# Domino_JTAG_No_Teardrop.net
KiCad netlist of a schematic drawn in EAGLE
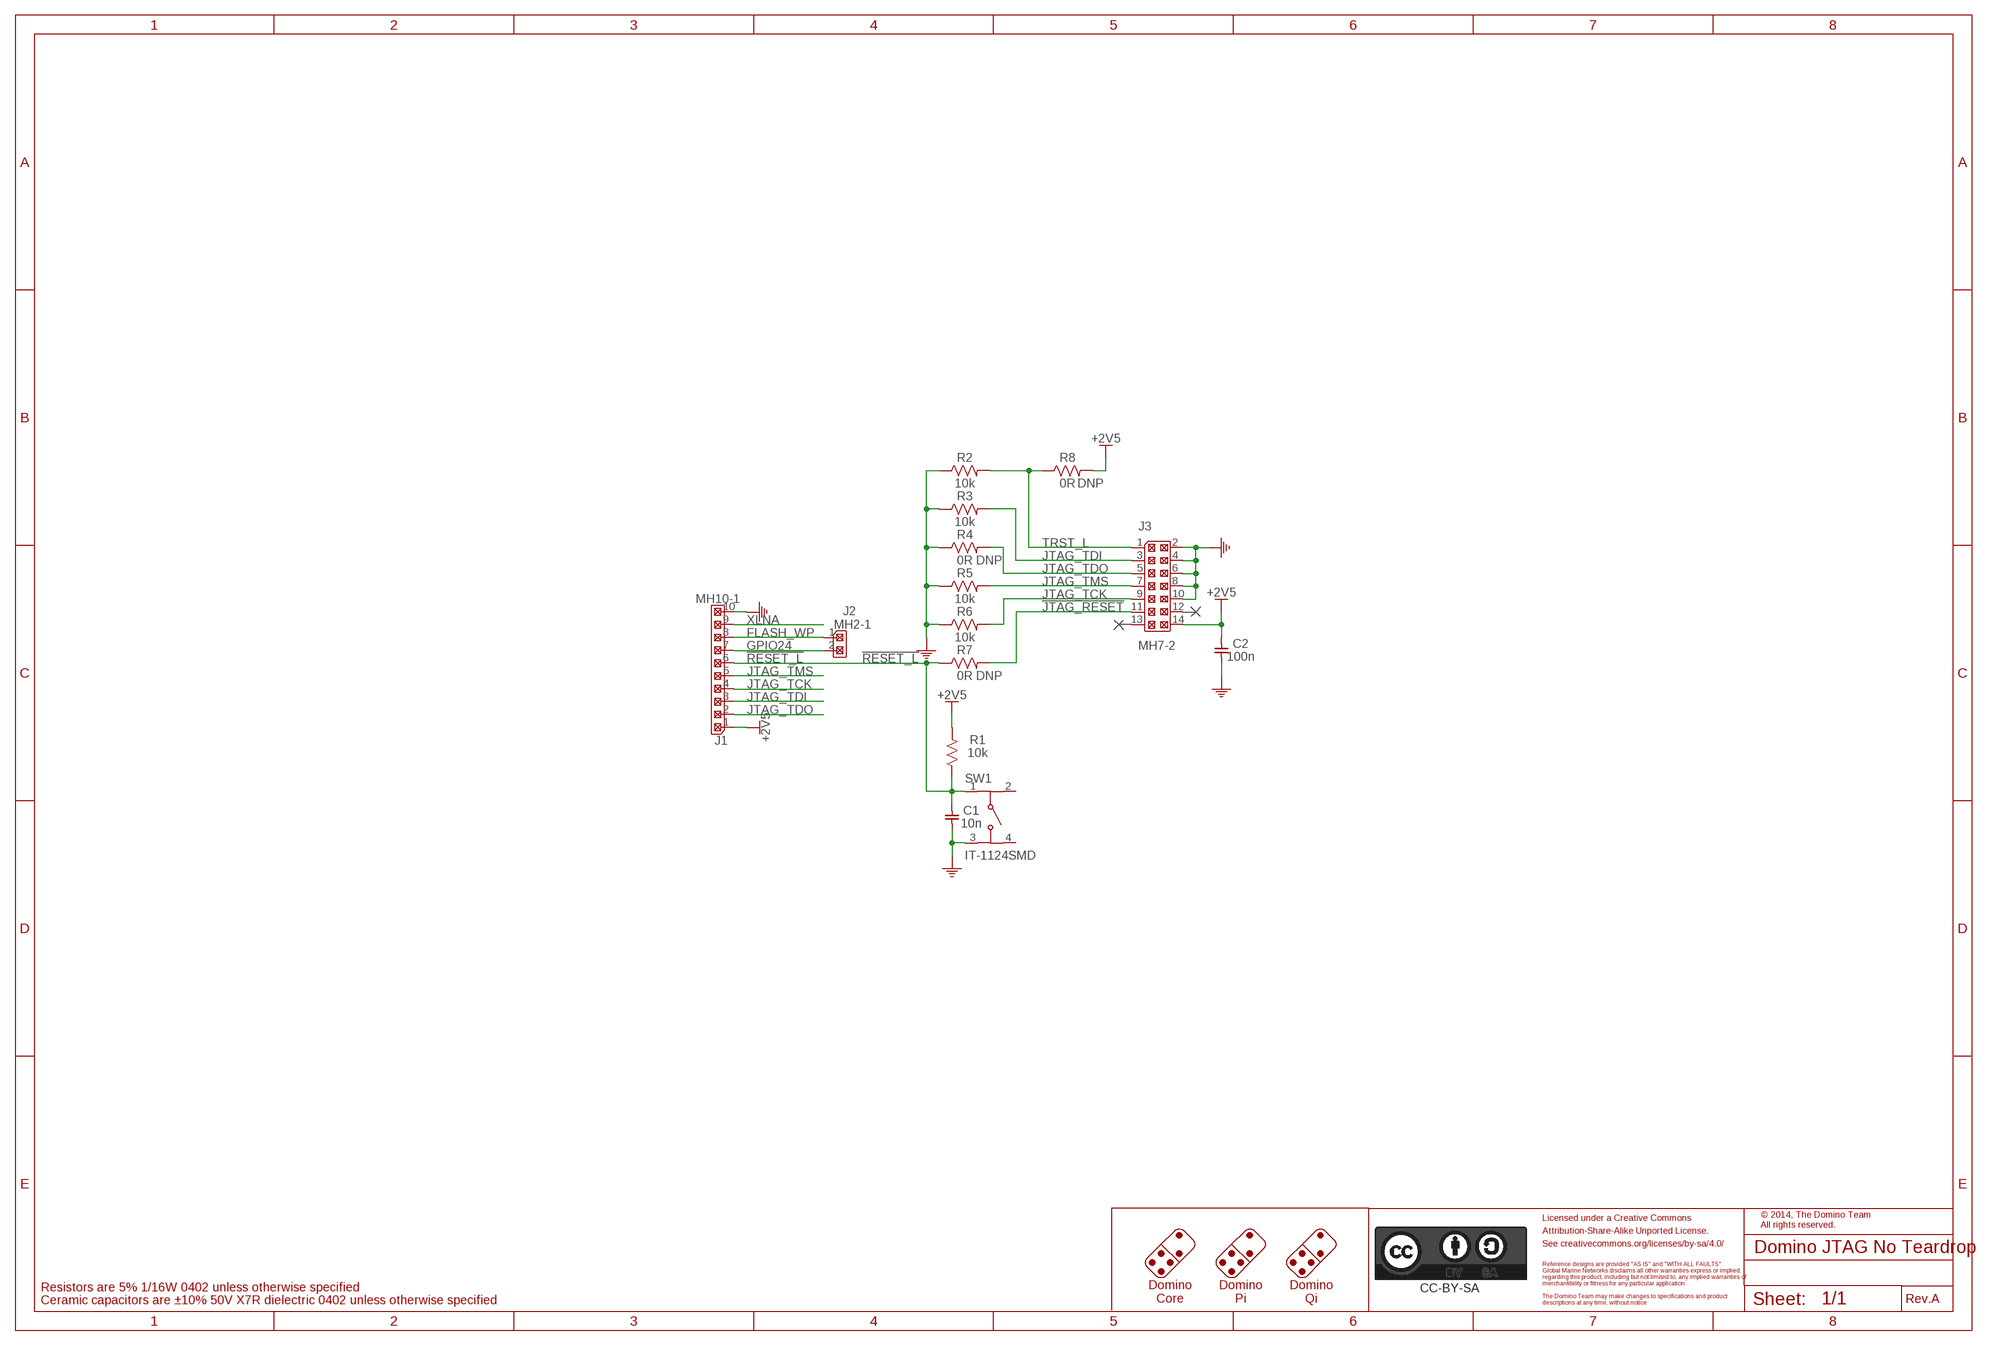
[diagram p0: schematic, sheet 1]

(export (version "E")
  (design (tool "Eeschema 10.0.6"))
  (components
    (comp (ref "C1")
      (value "10n")
      (footprint "eagle-import:C0402")
      (fields (field (name "PARTNO") "C0402_10n_X7R_10%_CER_50V"))
      (libsource (lib "eagle-import") (part "CAP_0402"))
    )
    (comp (ref "C2")
      (value "100n")
      (footprint "eagle-import:C0402")
      (fields (field (name "PARTNO") "C0402_100n_X7R_10%_CER_50V"))
      (libsource (lib "eagle-import") (part "CAP_0402"))
    )
    (comp (ref "CC-BY-SA1")
      (value "CC-BY-SA_LOGO")
      (footprint "eagle-import:CC-BY-SA_LOGO")
      (libsource (lib "eagle-import") (part "CC-BY-SA_LOGO"))
    )
    (comp (ref "J1")
      (value "MH10-1")
      (footprint "eagle-import:MH10-1-0.1")
      (fields (field (name "PARTNO") "MH10-1-0.1"))
      (libsource (lib "eagle-import") (part "MH10-1"))
    )
    (comp (ref "J2")
      (value "MH2-1")
      (footprint "eagle-import:MH2-1-0.1")
      (fields (field (name "PARTNO") "MH2-1-0.1"))
      (libsource (lib "eagle-import") (part "MH2-1"))
    )
    (comp (ref "J3")
      (value "MH7-2")
      (footprint "eagle-import:MH7-2-0.1")
      (fields (field (name "PARTNO") "MH7-2-0.1"))
      (libsource (lib "eagle-import") (part "MH7-2"))
    )
    (comp (ref "R1")
      (value "10k")
      (footprint "eagle-import:R0402")
      (fields (field (name "PARTNO") "R0402_10k_5%_62.5mW"))
      (libsource (lib "eagle-import") (part "RES_0402"))
    )
    (comp (ref "R2")
      (value "10k")
      (footprint "eagle-import:R0402")
      (fields (field (name "PARTNO") "R0402_10k_5%_62.5mW"))
      (libsource (lib "eagle-import") (part "RES_0402"))
    )
    (comp (ref "R3")
      (value "10k")
      (footprint "eagle-import:R0402")
      (fields (field (name "PARTNO") "R0402_10k_5%_62.5mW"))
      (libsource (lib "eagle-import") (part "RES_0402"))
    )
    (comp (ref "R4")
      (value "0R")
      (footprint "eagle-import:R0603")
      (fields (field (name "PARTNO") "R0603_0R_5%_125mW"))
      (libsource (lib "eagle-import") (part "RES_0603"))
    )
    (comp (ref "R5")
      (value "10k")
      (footprint "eagle-import:R0402")
      (fields (field (name "PARTNO") "R0402_10k_5%_62.5mW"))
      (libsource (lib "eagle-import") (part "RES_0402"))
    )
    (comp (ref "R6")
      (value "10k")
      (footprint "eagle-import:R0402")
      (fields (field (name "PARTNO") "R0402_10k_5%_62.5mW"))
      (libsource (lib "eagle-import") (part "RES_0402"))
    )
    (comp (ref "R7")
      (value "0R")
      (footprint "eagle-import:R0603")
      (fields (field (name "PARTNO") "R0603_0R_5%_125mW"))
      (libsource (lib "eagle-import") (part "RES_0603"))
    )
    (comp (ref "R8")
      (value "0R")
      (footprint "eagle-import:R0603")
      (fields (field (name "PARTNO") "R0603_0R_5%_125mW"))
      (libsource (lib "eagle-import") (part "RES_0603"))
    )
    (comp (ref "SW1")
      (value "IT-1124SMD")
      (footprint "eagle-import:IT-1124SMD")
      (libsource (lib "eagle-import") (part "IT-1124SMD"))
    )
  )
  (nets
    (net (code "1") (name "+2V5") (class "Default")
      (node (ref "C2") (pin "1") (pinfunction "1_1") (pintype "passive"))
      (node (ref "J1") (pin "1") (pinfunction "1_1") (pintype "passive"))
      (node (ref "J3") (pin "14") (pinfunction "14_14") (pintype "passive"))
      (node (ref "R1") (pin "2") (pinfunction "2_2") (pintype "passive"))
      (node (ref "R8") (pin "2") (pinfunction "2_2") (pintype "passive"))
    )
    (net (code "2") (name "/FLASH_WP") (class "Default")
      (node (ref "J1") (pin "8") (pinfunction "8_8") (pintype "passive"))
      (node (ref "J2") (pin "1") (pinfunction "1_1") (pintype "passive"))
    )
    (net (code "3") (name "/GPIO24") (class "Default")
      (node (ref "J1") (pin "7") (pinfunction "7_7") (pintype "passive"))
      (node (ref "J2") (pin "2") (pinfunction "2_2") (pintype "passive"))
    )
    (net (code "4") (name "/JTAG_TCK") (class "Default")
      (node (ref "J1") (pin "4") (pinfunction "4_4") (pintype "passive"))
      (node (ref "J3") (pin "9") (pinfunction "9_9") (pintype "passive"))
      (node (ref "R6") (pin "2") (pinfunction "2_2") (pintype "passive"))
    )
    (net (code "5") (name "/JTAG_TDI") (class "Default")
      (node (ref "J1") (pin "3") (pinfunction "3_3") (pintype "passive"))
      (node (ref "J3") (pin "3") (pinfunction "3_3") (pintype "passive"))
      (node (ref "R3") (pin "2") (pinfunction "2_2") (pintype "passive"))
    )
    (net (code "6") (name "/JTAG_TDO") (class "Default")
      (node (ref "J1") (pin "2") (pinfunction "2_2") (pintype "passive"))
      (node (ref "J3") (pin "5") (pinfunction "5_5") (pintype "passive"))
      (node (ref "R4") (pin "2") (pinfunction "2_2") (pintype "passive"))
    )
    (net (code "7") (name "/JTAG_TMS") (class "Default")
      (node (ref "J1") (pin "5") (pinfunction "5_5") (pintype "passive"))
      (node (ref "J3") (pin "7") (pinfunction "7_7") (pintype "passive"))
      (node (ref "R5") (pin "2") (pinfunction "2_2") (pintype "passive"))
    )
    (net (code "8") (name "/TRST_L") (class "Default")
      (node (ref "J3") (pin "1") (pinfunction "1_1") (pintype "passive"))
      (node (ref "R2") (pin "2") (pinfunction "2_2") (pintype "passive"))
      (node (ref "R8") (pin "1") (pinfunction "1_1") (pintype "passive"))
    )
    (net (code "9") (name "/XLNA") (class "Default")
      (node (ref "J1") (pin "9") (pinfunction "9_9") (pintype "passive"))
    )
    (net (code "10") (name "/~{JTAG_RESET}") (class "Default")
      (node (ref "J3") (pin "11") (pinfunction "11_11") (pintype "passive"))
      (node (ref "R7") (pin "2") (pinfunction "2_2") (pintype "passive"))
    )
    (net (code "11") (name "/~{RESET_L}") (class "Default")
      (node (ref "C1") (pin "1") (pinfunction "1_1") (pintype "passive"))
      (node (ref "J1") (pin "6") (pinfunction "6_6") (pintype "passive"))
      (node (ref "R1") (pin "1") (pinfunction "1_1") (pintype "passive"))
      (node (ref "R7") (pin "1") (pinfunction "1_1") (pintype "passive"))
      (node (ref "SW1") (pin "1") (pinfunction "1_1") (pintype "passive"))
    )
    (net (code "12") (name "GND") (class "Default")
      (node (ref "C1") (pin "2") (pinfunction "2_2") (pintype "passive"))
      (node (ref "C2") (pin "2") (pinfunction "2_2") (pintype "passive"))
      (node (ref "J1") (pin "10") (pinfunction "10_10") (pintype "passive"))
      (node (ref "J3") (pin "10") (pinfunction "10_10") (pintype "passive"))
      (node (ref "J3") (pin "2") (pinfunction "2_2") (pintype "passive"))
      (node (ref "J3") (pin "4") (pinfunction "4_4") (pintype "passive"))
      (node (ref "J3") (pin "6") (pinfunction "6_6") (pintype "passive"))
      (node (ref "J3") (pin "8") (pinfunction "8_8") (pintype "passive"))
      (node (ref "R2") (pin "1") (pinfunction "1_1") (pintype "passive"))
      (node (ref "R3") (pin "1") (pinfunction "1_1") (pintype "passive"))
      (node (ref "R4") (pin "1") (pinfunction "1_1") (pintype "passive"))
      (node (ref "R5") (pin "1") (pinfunction "1_1") (pintype "passive"))
      (node (ref "R6") (pin "1") (pinfunction "1_1") (pintype "passive"))
      (node (ref "SW1") (pin "3") (pinfunction "3_3") (pintype "passive"))
    )
    (net (code "13") (name "unconnected-(J3-Pad12)") (class "Default")
      (node (ref "J3") (pin "12") (pinfunction "12_12") (pintype "passive"))
    )
    (net (code "14") (name "unconnected-(J3-Pad13)") (class "Default")
      (node (ref "J3") (pin "13") (pinfunction "13_13") (pintype "passive"))
    )
    (net (code "15") (name "unconnected-(SW1-Pad2)") (class "Default")
      (node (ref "SW1") (pin "2") (pinfunction "2_2") (pintype "passive"))
    )
    (net (code "16") (name "unconnected-(SW1-Pad4)") (class "Default")
      (node (ref "SW1") (pin "4") (pinfunction "4_4") (pintype "passive"))
    )
  )
)
